# nfc_3911_sch.net
KiCad netlist of a schematic drawn in Altium Designer
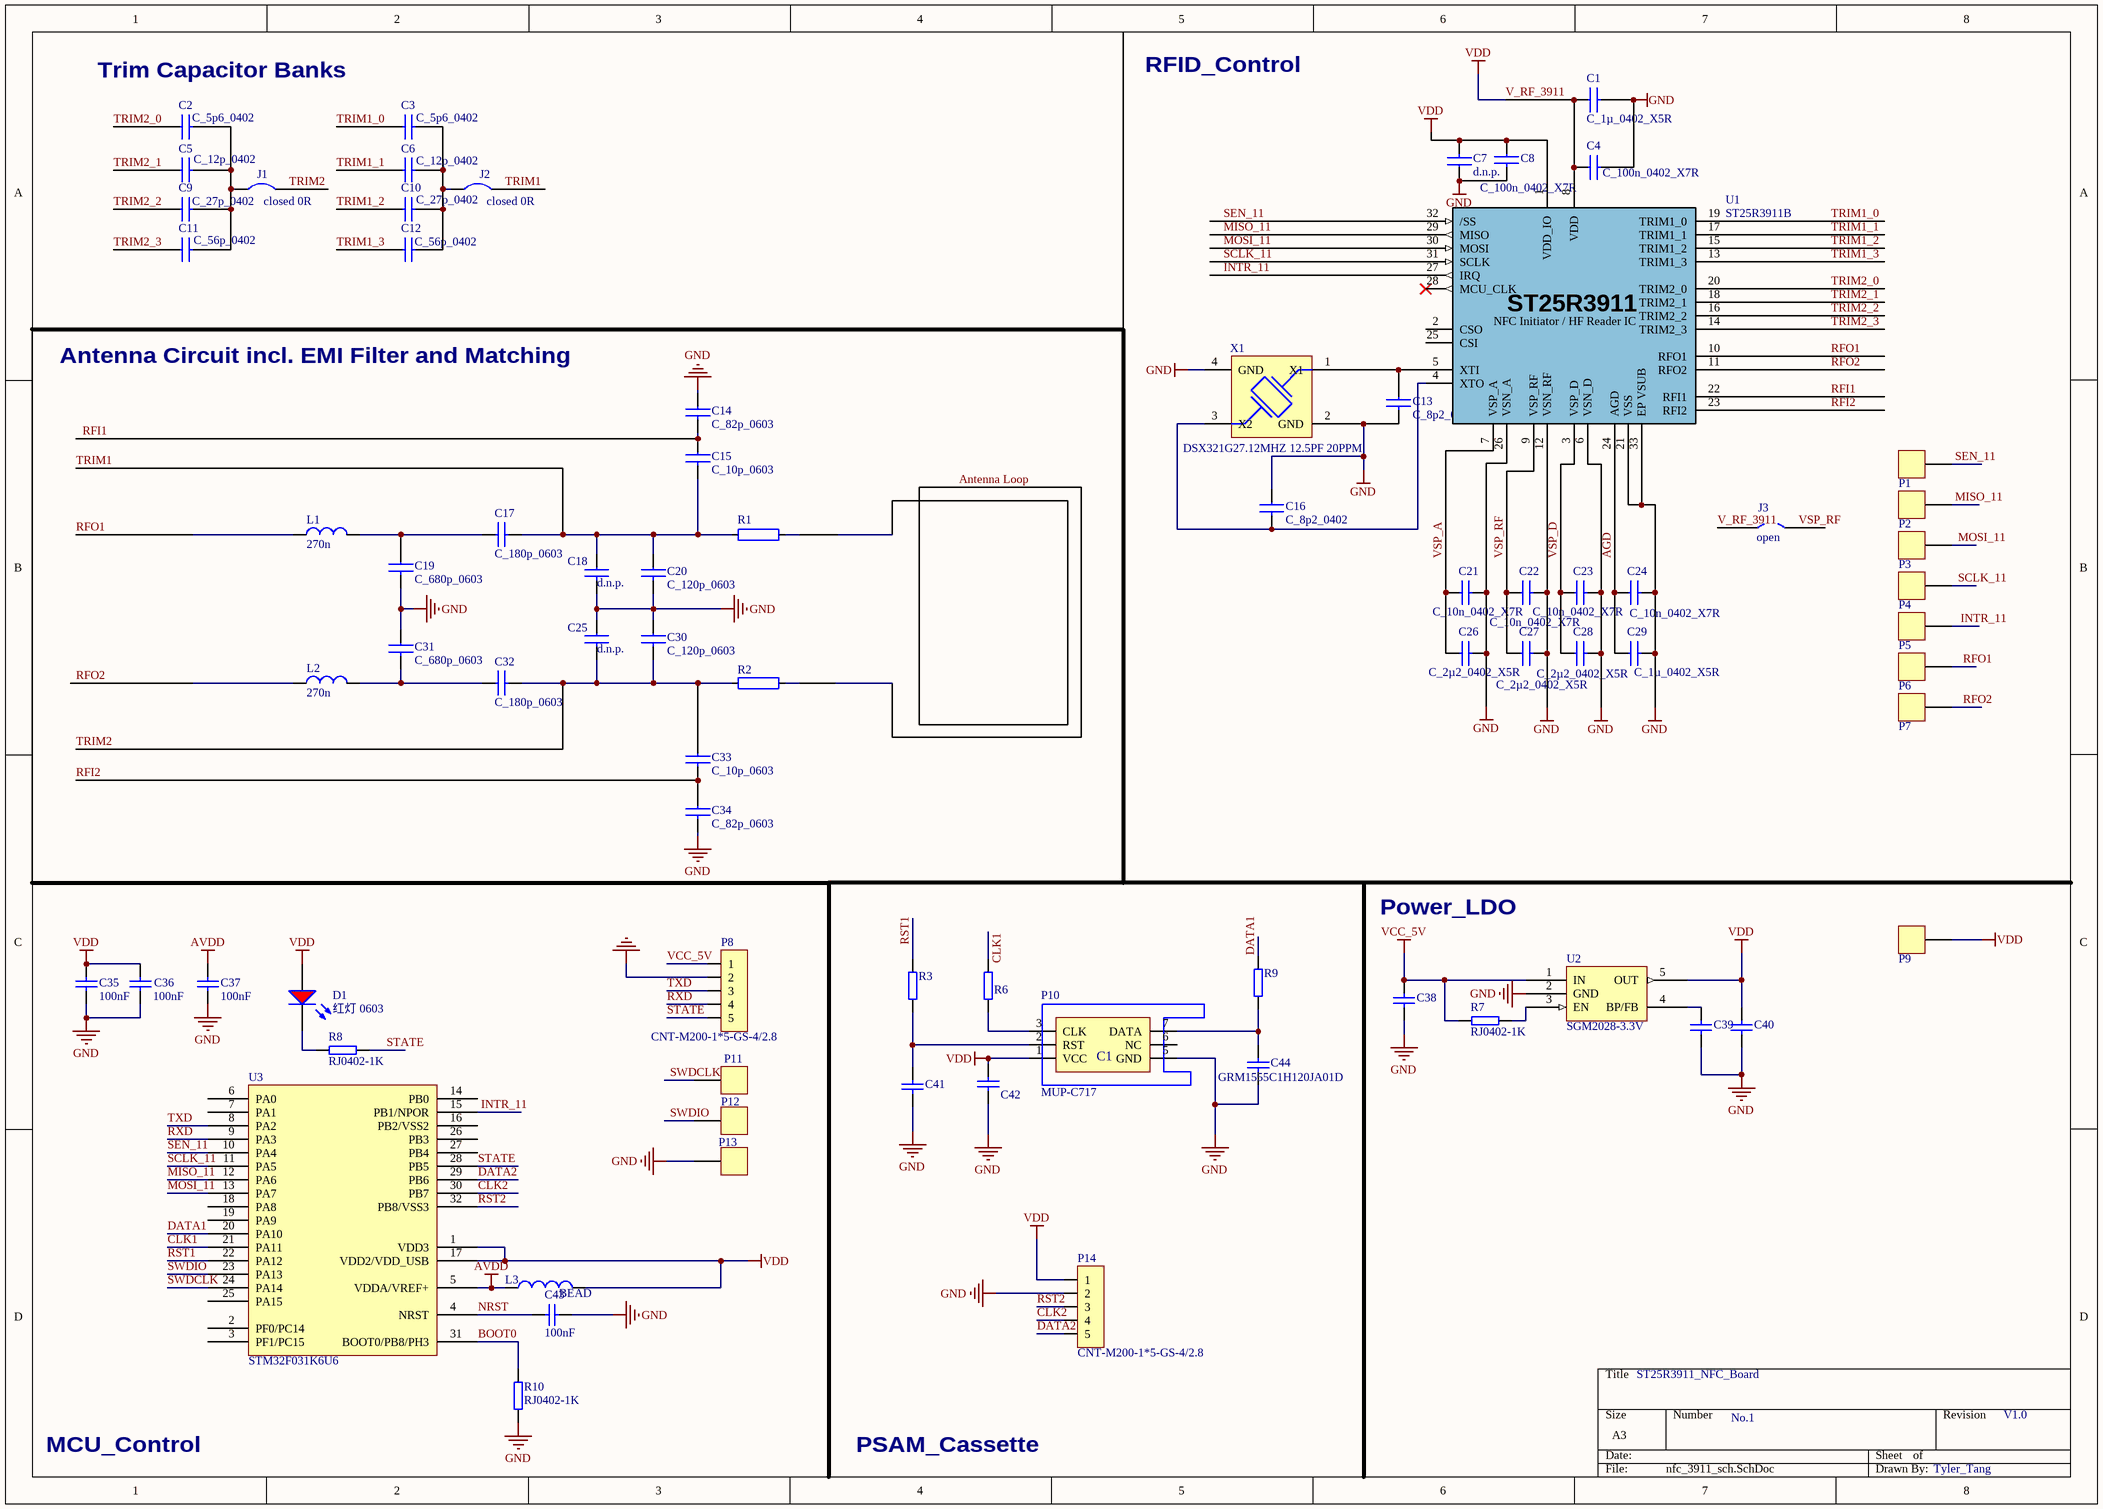
[diagram p0: nfc_3911_sch.SchDoc]

(export (version "E")
  (design (tool "Eeschema 10.0.6"))
  (components
    (comp (ref "C1")
      (value "C_1µ_0402_X5R")
      (footprint "0402_C")
      (description "1u_X5R")
      (fields
        (field (name "MANUFACTURER") "MURATA")
        (field (name "MANUFACTURER PART NUMBER") "GRM155R61C105KA12D")
      )
      (libsource (lib "Schlib1") (part "C_1µ_0402_X5R"))
    )
    (comp (ref "C2")
      (value "C_5p6_0402")
      (footprint "0402_C")
      (description "5p6_COG")
      (fields
        (field (name "MANUFACTURER") "MURATA")
        (field (name "MANUFACTURER PART NUMBER") "GRM1555C1H5R6DA01D")
      )
      (libsource (lib "Schlib1") (part "C_5p6_0402"))
    )
    (comp (ref "C3")
      (value "C_5p6_0402")
      (footprint "0402_C")
      (description "5p6_COG")
      (fields
        (field (name "MANUFACTURER") "MURATA")
        (field (name "MANUFACTURER PART NUMBER") "GRM1555C1H5R6DA01D")
      )
      (libsource (lib "Schlib1") (part "C_5p6_0402"))
    )
    (comp (ref "C4")
      (value "C_100n_0402_X7R")
      (footprint "0402_C")
      (description "100n_X7R")
      (fields
        (field (name "MANUFACTURER") "MULTICOMP")
        (field (name "MANUFACTURER PART NUMBER") "MC0402X104K100CT")
      )
      (libsource (lib "Schlib1") (part "C_100n_0402_X7R"))
    )
    (comp (ref "C5")
      (value "C_12p_0402")
      (footprint "0402_C")
      (description "12p_COG")
      (fields
        (field (name "MANUFACTURER") "MURATA")
        (field (name "MANUFACTURER PART NUMBER") "GRM1555C1H120GA01D")
      )
      (libsource (lib "Schlib1") (part "C_12p_0402"))
    )
    (comp (ref "C6")
      (value "C_12p_0402")
      (footprint "0402_C")
      (description "12p_COG")
      (fields
        (field (name "MANUFACTURER") "MURATA")
        (field (name "MANUFACTURER PART NUMBER") "GRM1555C1H120GA01D")
      )
      (libsource (lib "Schlib1") (part "C_12p_0402"))
    )
    (comp (ref "C7") (value "d.n.p.") (footprint "0402_C") (libsource (lib "PASSIVE_082011") (part "C_0402")))
    (comp (ref "C8")
      (value "C_100n_0402_X7R")
      (footprint "0402_C")
      (description "100n_X7R")
      (fields
        (field (name "MANUFACTURER") "MULTICOMP")
        (field (name "MANUFACTURER PART NUMBER") "MC0402X104K100CT")
      )
      (libsource (lib "Schlib1") (part "C_100n_0402_X7R"))
    )
    (comp (ref "C9")
      (value "C_27p_0402")
      (footprint "0402_C")
      (description "27p_COG")
      (fields
        (field (name "MANUFACTURER") "MURATA")
        (field (name "MANUFACTURER PART NUMBER") "GRM1555C1H270GA01D")
      )
      (libsource (lib "Schlib1") (part "C_27p_0402"))
    )
    (comp (ref "C10")
      (value "C_27p_0402")
      (footprint "0402_C")
      (description "27p_COG")
      (fields
        (field (name "MANUFACTURER") "MURATA")
        (field (name "MANUFACTURER PART NUMBER") "GRM1555C1H270GA01D")
      )
      (libsource (lib "Schlib1") (part "C_27p_0402"))
    )
    (comp (ref "C11")
      (value "C_56p_0402")
      (footprint "0402_C")
      (description "56p_COG")
      (fields
        (field (name "MANUFACTURER") "MURATA")
        (field (name "MANUFACTURER PART NUMBER") "GRM1555C1H560GA01D")
      )
      (libsource (lib "Schlib1") (part "C_56p_0402"))
    )
    (comp (ref "C12")
      (value "C_56p_0402")
      (footprint "0402_C")
      (description "56p_COG")
      (fields
        (field (name "MANUFACTURER") "MURATA")
        (field (name "MANUFACTURER PART NUMBER") "GRM1555C1H560GA01D")
      )
      (libsource (lib "Schlib1") (part "C_56p_0402"))
    )
    (comp (ref "C13")
      (value "C_8p2_0402")
      (footprint "0402_C")
      (description "8p2_COG")
      (fields
        (field (name "MANUFACTURER") "MURATA")
        (field (name "MANUFACTURER PART NUMBER") "GRM1555C1H8R2CA01D")
      )
      (libsource (lib "Schlib1") (part "C_8p2_0402"))
    )
    (comp (ref "C14")
      (value "C_82p_0603")
      (footprint "0603_C")
      (description "82p_COG")
      (fields
        (field (name "MANUFACTURER") "MURATA")
        (field (name "MANUFACTURER PART NUMBER") "GRM1885C1H820FA01D")
      )
      (libsource (lib "Schlib1") (part "C_82p_0603"))
    )
    (comp (ref "C15")
      (value "C_10p_0603")
      (footprint "0603_C")
      (description "10p_COG")
      (fields
        (field (name "MANUFACTURER") "MULTICOMP")
        (field (name "MANUFACTURER PART NUMBER") "MC0603N100F500CT")
      )
      (libsource (lib "Schlib1") (part "C_10p_0603"))
    )
    (comp (ref "C16")
      (value "C_8p2_0402")
      (footprint "0402_C")
      (description "8p2_COG")
      (fields
        (field (name "MANUFACTURER") "MURATA")
        (field (name "MANUFACTURER PART NUMBER") "GRM1555C1H8R2CA01D")
      )
      (libsource (lib "Schlib1") (part "C_8p2_0402"))
    )
    (comp (ref "C17")
      (value "C_180p_0603")
      (footprint "0603_C")
      (description "180p_COG")
      (fields
        (field (name "MANUFACTURER") "MURATA")
        (field (name "MANUFACTURER PART NUMBER") "GRM1885C1H181GA01D")
      )
      (libsource (lib "Schlib1") (part "C_180p_0603"))
    )
    (comp (ref "C18")
      (value "d.n.p.")
      (footprint "0603_C")
      (libsource (lib "PASSIVE_082011") (part "C_0603"))
    )
    (comp (ref "C19")
      (value "C_680p_0603")
      (footprint "0603_C")
      (description "680p_COG")
      (fields
        (field (name "MANUFACTURER") "MURATA")
        (field (name "MANUFACTURER PART NUMBER") "GRM1885C1H681GA01D")
      )
      (libsource (lib "Schlib1") (part "C_680p_0603"))
    )
    (comp (ref "C20")
      (value "C_120p_0603")
      (footprint "0603_C")
      (description "120p_COG")
      (fields
        (field (name "MANUFACTURER") "MURATA")
        (field (name "MANUFACTURER PART NUMBER") "GRM1885C1H121GA01D")
      )
      (libsource (lib "Schlib1") (part "C_120p_0603"))
    )
    (comp (ref "C21")
      (value "C_10n_0402_X7R")
      (footprint "0402_C")
      (description "10n_x7R")
      (fields (field (name "MANUFACTURER") "AVX") (field (name "MANUFACTURER PART NUMBER") "04023C103KAT2A"))
      (libsource (lib "Schlib1") (part "C_10n_0402_X7R"))
    )
    (comp (ref "C22")
      (value "C_10n_0402_X7R")
      (footprint "0402_C")
      (description "10n_x7R")
      (fields (field (name "MANUFACTURER") "AVX") (field (name "MANUFACTURER PART NUMBER") "04023C103KAT2A"))
      (libsource (lib "Schlib1") (part "C_10n_0402_X7R"))
    )
    (comp (ref "C23")
      (value "C_10n_0402_X7R")
      (footprint "0402_C")
      (description "10n_x7R")
      (fields (field (name "MANUFACTURER") "AVX") (field (name "MANUFACTURER PART NUMBER") "04023C103KAT2A"))
      (libsource (lib "Schlib1") (part "C_10n_0402_X7R"))
    )
    (comp (ref "C24")
      (value "C_10n_0402_X7R")
      (footprint "0402_C")
      (description "10n_x7R")
      (fields (field (name "MANUFACTURER") "AVX") (field (name "MANUFACTURER PART NUMBER") "04023C103KAT2A"))
      (libsource (lib "Schlib1") (part "C_10n_0402_X7R"))
    )
    (comp (ref "C25")
      (value "d.n.p.")
      (footprint "0603_C")
      (libsource (lib "PASSIVE_082011") (part "C_0603"))
    )
    (comp (ref "C26")
      (value "C_2µ2_0402_X5R")
      (footprint "0402_C")
      (description "2u2_X5R")
      (fields
        (field (name "MANUFACTURER") "MURATA")
        (field (name "MANUFACTURER PART NUMBER") "GRM155R60J225ME15D")
      )
      (libsource (lib "Schlib1") (part "C_2µ2_0402_X5R"))
    )
    (comp (ref "C27")
      (value "C_2µ2_0402_X5R")
      (footprint "0402_C")
      (description "2u2_X5R")
      (fields
        (field (name "MANUFACTURER") "MURATA")
        (field (name "MANUFACTURER PART NUMBER") "GRM155R60J225ME15D")
      )
      (libsource (lib "Schlib1") (part "C_2µ2_0402_X5R"))
    )
    (comp (ref "C28")
      (value "C_2µ2_0402_X5R")
      (footprint "0402_C")
      (description "2u2_X5R")
      (fields
        (field (name "MANUFACTURER") "MURATA")
        (field (name "MANUFACTURER PART NUMBER") "GRM155R60J225ME15D")
      )
      (libsource (lib "Schlib1") (part "C_2µ2_0402_X5R"))
    )
    (comp (ref "C29")
      (value "C_1µ_0402_X5R")
      (footprint "0402_C")
      (description "1u_X5R")
      (fields
        (field (name "MANUFACTURER") "MURATA")
        (field (name "MANUFACTURER PART NUMBER") "GRM155R61C105KA12D")
      )
      (libsource (lib "Schlib1") (part "C_1µ_0402_X5R"))
    )
    (comp (ref "C30")
      (value "C_120p_0603")
      (footprint "0603_C")
      (description "120p_COG")
      (fields
        (field (name "MANUFACTURER") "MURATA")
        (field (name "MANUFACTURER PART NUMBER") "GRM1885C1H121GA01D")
      )
      (libsource (lib "Schlib1") (part "C_120p_0603"))
    )
    (comp (ref "C31")
      (value "C_680p_0603")
      (footprint "0603_C")
      (description "680p_COG")
      (fields
        (field (name "MANUFACTURER") "MURATA")
        (field (name "MANUFACTURER PART NUMBER") "GRM1885C1H681GA01D")
      )
      (libsource (lib "Schlib1") (part "C_680p_0603"))
    )
    (comp (ref "C32")
      (value "C_180p_0603")
      (footprint "0603_C")
      (description "180p_COG")
      (fields
        (field (name "MANUFACTURER") "MURATA")
        (field (name "MANUFACTURER PART NUMBER") "GRM1885C1H181GA01D")
      )
      (libsource (lib "Schlib1") (part "C_180p_0603"))
    )
    (comp (ref "C33")
      (value "C_10p_0603")
      (footprint "0603_C")
      (description "10p_COG")
      (fields
        (field (name "MANUFACTURER") "MULTICOMP")
        (field (name "MANUFACTURER PART NUMBER") "MC0603N100F500CT")
      )
      (libsource (lib "Schlib1") (part "C_10p_0603"))
    )
    (comp (ref "C34")
      (value "C_82p_0603")
      (footprint "0603_C")
      (description "82p_COG")
      (fields
        (field (name "MANUFACTURER") "MURATA")
        (field (name "MANUFACTURER PART NUMBER") "GRM1885C1H820FA01D")
      )
      (libsource (lib "Schlib1") (part "C_82p_0603"))
    )
    (comp (ref "C35")
      (value "100nF")
      (footprint "0402_C")
      (description "Capacitor")
      (fields (field (name "PUBLISHER") "Altium Limited"))
      (libsource (lib "Miscellaneous Devices") (part "Cap"))
    )
    (comp (ref "C36")
      (value "100nF")
      (footprint "0402_C")
      (description "Capacitor")
      (fields (field (name "PUBLISHER") "Altium Limited"))
      (libsource (lib "Miscellaneous Devices") (part "Cap"))
    )
    (comp (ref "C37")
      (value "100nF")
      (footprint "0402_C")
      (description "Capacitor")
      (fields (field (name "PUBLISHER") "Altium Limited"))
      (libsource (lib "Miscellaneous Devices") (part "Cap"))
    )
    (comp (ref "C38")
      (value "CAP-NP")
      (footprint "0402_C")
      (description "1uF/6.3V/10%/X5R")
      (libsource (lib "LSD Altium") (part "CAP-NP"))
    )
    (comp (ref "C39")
      (value "CAP-NP")
      (footprint "0402_C")
      (description "1uF/6.3V/10%/X5R")
      (libsource (lib "LSD Altium") (part "CAP-NP"))
    )
    (comp (ref "C40")
      (value "CAP-NP")
      (footprint "0402_C")
      (description "10nF/25V/10%/X7R")
      (libsource (lib "LSD Altium") (part "CAP-NP"))
    )
    (comp (ref "C41")
      (value "CAP-NP")
      (footprint "0402_C")
      (description "0.1uF/16V/10%/X5R")
      (libsource (lib "LSD Altium") (part "CAP-NP"))
    )
    (comp (ref "C42")
      (value "CAP-NP")
      (footprint "0402_C")
      (description "0.1uF/16V/10%/X5R")
      (libsource (lib "LSD Altium") (part "CAP-NP"))
    )
    (comp (ref "C43")
      (value "100nF")
      (footprint "0402_C")
      (description "Capacitor")
      (fields (field (name "PUBLISHER") "Altium Limited"))
      (libsource (lib "Miscellaneous Devices") (part "CAP"))
    )
    (comp (ref "C44")
      (value "CAP-NP")
      (footprint "0402C_0.4D")
      (description "12pF/50V/5%/C0G")
      (fields (field (name "产品型号") "GRM1555C1H120JA01D"))
      (libsource (lib "LSD Altium") (part "CAP-NP"))
    )
    (comp (ref "D1")
      (value "红灯 0603")
      (footprint "0603_LED_S1")
      (description "发光二极管")
      (libsource (lib "LED") (part "0603 红灯"))
    )
    (comp (ref "J1")
      (value "closed 0R")
      (footprint "0402_R")
      (description "0R")
      (fields
        (field (name "MANUFACTURER") "Multicomp")
        (field (name "MANUFACTURER PART NUMBER") "MC00625W040210R")
      )
      (libsource (lib "Schlib1") (part "solder_jumper_closed"))
    )
    (comp (ref "J2")
      (value "closed 0R")
      (footprint "0402_R")
      (description "0R")
      (fields
        (field (name "MANUFACTURER") "Multicomp")
        (field (name "MANUFACTURER PART NUMBER") "MC00625W040210R")
      )
      (libsource (lib "Schlib1") (part "solder_jumper_closed"))
    )
    (comp (ref "J3")
      (value "open")
      (footprint "0402_R")
      (libsource (lib "Schlib1") (part "solder_jumper_open"))
    )
    (comp (ref "L1")
      (value "270n")
      (footprint "0603_L")
      (description "L0603_270nH")
      (fields
        (field (name "MANUFACTURER") "MURATA")
        (field (name "MANUFACTURER PART NUMBER") "LQW18ANR27G80D")
      )
      (libsource (lib "Schlib1") (part "L0603_270nH"))
    )
    (comp (ref "L2")
      (value "270n")
      (footprint "0603_L")
      (description "L0603_270nH")
      (fields
        (field (name "MANUFACTURER") "MURATA")
        (field (name "MANUFACTURER PART NUMBER") "LQW18ANR27G80D")
      )
      (libsource (lib "Schlib1") (part "L0603_270nH"))
    )
    (comp (ref "L3")
      (value "BEAD")
      (footprint "0603")
      (description "Inductor")
      (fields (field (name "PUBLISHER") "Altium Limited"))
      (libsource (lib "Miscellaneous Devices") (part "Inductor"))
    )
    (comp (ref "P1") (value "Hole") (footprint "TP1") (libsource (lib "4_1 EcoSys") (part "Hole")))
    (comp (ref "P2") (value "Hole") (footprint "TP1") (libsource (lib "4_1 EcoSys") (part "Hole")))
    (comp (ref "P3") (value "Hole") (footprint "TP1") (libsource (lib "4_1 EcoSys") (part "Hole")))
    (comp (ref "P4") (value "Hole") (footprint "TP1") (libsource (lib "4_1 EcoSys") (part "Hole")))
    (comp (ref "P5") (value "Hole") (footprint "TP1") (libsource (lib "4_1 EcoSys") (part "Hole")))
    (comp (ref "P6") (value "Hole") (footprint "TP1") (libsource (lib "4_1 EcoSys") (part "Hole")))
    (comp (ref "P7") (value "Hole") (footprint "TP1") (libsource (lib "4_1 EcoSys") (part "Hole")))
    (comp (ref "P8")
      (value "SPI 5-M")
      (footprint "SIP 2.0_5_S")
      (description "2.00mm/1*5P/单排/直/PA=4/PC=2.8")
      (fields (field (name "产品型号") "CNT-M200-1*5-GS-4/2.8"))
      (libsource (lib "LSD Altium") (part "SPI 5-M"))
    )
    (comp (ref "P9") (value "Hole") (footprint "TP1") (libsource (lib "4_1 EcoSys") (part "Hole")))
    (comp (ref "P10")
      (value "SIM-4")
      (footprint "SIM-MUP-C717")
      (description "SIM卡座")
      (fields (field (name "产品型号") "MUP-C717"))
      (libsource (lib "LSD Altium") (part "SIM-4"))
    )
    (comp (ref "P11") (value "Hole") (footprint "TP1") (libsource (lib "") (part "Hole_1")))
    (comp (ref "P12") (value "Hole") (footprint "TP1") (libsource (lib "") (part "Hole_1")))
    (comp (ref "P13") (value "Hole") (footprint "TP1") (libsource (lib "") (part "Hole_1")))
    (comp (ref "P14")
      (value "SPI 5-M")
      (footprint "SIP 2.0_5_S")
      (description "2.00mm/1*5P/单排/直/PA=4/PC=2.8")
      (fields (field (name "产品型号") "CNT-M200-1*5-GS-4/2.8"))
      (libsource (lib "LSD Altium") (part "SPI 5-M"))
    )
    (comp (ref "R1")
      (value "3R9")
      (footprint "0603_R")
      (description "3R9, 0603")
      (fields
        (field (name "MANUFACTURER") "Panasonic")
        (field (name "MANUFACTURER PART NUMBER") "ERJ-3GEYJ3R9V")
      )
      (libsource (lib "Schlib1") (part "R0603_3R9"))
    )
    (comp (ref "R2")
      (value "3R9")
      (footprint "0603_R")
      (description "3R9, 0603")
      (fields
        (field (name "MANUFACTURER") "Panasonic")
        (field (name "MANUFACTURER PART NUMBER") "ERJ-3GEYJ3R9V")
      )
      (libsource (lib "Schlib1") (part "R0603_3R9"))
    )
    (comp (ref "R3")
      (value "RES")
      (footprint "0402R_0.4D")
      (description "33R/5%/100PPM")
      (libsource (lib "LSD Altium") (part "RES"))
    )
    (comp (ref "R6")
      (value "RES")
      (footprint "0402R_0.4D")
      (description "33R/5%/100PPM")
      (libsource (lib "LSD Altium") (part "RES"))
    )
    (comp (ref "R7")
      (value "RES")
      (footprint "0402R_0.4D")
      (description "1K/5%/100PPM")
      (fields (field (name "产品型号") "RJ0402-1K"))
      (libsource (lib "LSD Altium") (part "RES"))
    )
    (comp (ref "R8")
      (value "RES")
      (footprint "0402R_0.4D")
      (description "1K/5%/100PPM")
      (fields (field (name "产品型号") "RJ0402-1K"))
      (libsource (lib "LSD Altium") (part "RES"))
    )
    (comp (ref "R9")
      (value "RES")
      (footprint "0402R_0.4D")
      (description "33R/5%/100PPM")
      (libsource (lib "LSD Altium") (part "RES"))
    )
    (comp (ref "R10")
      (value "RES")
      (footprint "0402R_0.4D")
      (description "1K/5%/100PPM")
      (fields (field (name "产品型号") "RJ0402-1K"))
      (libsource (lib "LSD Altium") (part "RES"))
    )
    (comp (ref "U1")
      (value "ST25R3911B")
      (footprint "ST25R3911B")
      (description "NFC Initiator / HF Reader IC")
      (fields
        (field (name "MANUFACTURER") "STMicroelectronics")
        (field (name "MANUFACTURER PART NUMBER") "ST25R3911B-AQFMCT-ND")
      )
      (libsource (lib "Schlib1") (part "ST25R3911"))
    )
    (comp (ref "U2")
      (value "SGM2028-3.3V")
      (footprint "SGM2028-3.3")
      (libsource (lib "nfc_3911_schLib") (part "SGM2028"))
    )
    (comp (ref "U3")
      (value "STM32F031K6U6")
      (footprint "STM32F031K6U6")
      (libsource (lib "MB1180") (part "MCU_LQFP32"))
    )
    (comp (ref "X1")
      (value "CRYSTAL-4P")
      (footprint "2520")
      (description "10pF/40MHz/10PPM/60Ωmax/-40°~85°")
      (fields (field (name "产品型号") "DSX321G27.12MHZ 12.5PF 20PPM"))
      (libsource (lib "LSD Altium") (part "CRYSTAL-4P"))
    )
  )
  (nets
    (net (code "1") (name "/AGD") (class "Default")
      (node (ref "C24") (pin "1") (pinfunction "1_1") (pintype "passive"))
      (node (ref "C29") (pin "1") (pinfunction "1_1") (pintype "passive"))
      (node (ref "U1") (pin "24") (pinfunction "AGD_24") (pintype "passive"))
    )
    (net (code "2") (name "/Antenna Loop") (class "Default")
      (node (ref "R1") (pin "1") (pinfunction "1_1") (pintype "passive"))
      (node (ref "R2") (pin "1") (pinfunction "1_1") (pintype "passive"))
    )
    (net (code "3") (name "/BOOT0") (class "Default")
      (node (ref "R10") (pin "1") (pinfunction "1_1") (pintype "passive"))
      (node (ref "U3") (pin "31") (pinfunction "BOOT0/PB8/PH3_31") (pintype "passive"))
    )
    (net (code "4") (name "/CLK1") (class "Default")
      (node (ref "R6") (pin "1") (pinfunction "1_1") (pintype "passive"))
      (node (ref "U3") (pin "21") (pinfunction "PA11_21") (pintype "passive"))
    )
    (net (code "5") (name "/CLK2") (class "Default")
      (node (ref "P14") (pin "4") (pinfunction "4_4") (pintype "passive"))
      (node (ref "U3") (pin "30") (pinfunction "PB7_30") (pintype "passive"))
    )
    (net (code "6") (name "/DATA1") (class "Default")
      (node (ref "R9") (pin "2") (pinfunction "2_2") (pintype "passive"))
      (node (ref "U3") (pin "20") (pinfunction "PA10_20") (pintype "passive"))
    )
    (net (code "7") (name "/DATA2") (class "Default")
      (node (ref "P14") (pin "5") (pinfunction "5_5") (pintype "passive"))
      (node (ref "U3") (pin "29") (pinfunction "PB6_29") (pintype "passive"))
    )
    (net (code "8") (name "/INTR_11") (class "Default")
      (node (ref "P5") (pin "1") (pinfunction "1_1") (pintype "passive"))
      (node (ref "U1") (pin "27") (pinfunction "IRQ_27") (pintype "output"))
      (node (ref "U3") (pin "15") (pinfunction "PB1/NPOR_15") (pintype "passive"))
    )
    (net (code "9") (name "/MISO_11") (class "Default")
      (node (ref "P2") (pin "1") (pinfunction "1_1") (pintype "passive"))
      (node (ref "U1") (pin "29") (pinfunction "MISO_29") (pintype "output"))
      (node (ref "U3") (pin "12") (pinfunction "PA6_12") (pintype "passive"))
    )
    (net (code "10") (name "/MOSI_11") (class "Default")
      (node (ref "P3") (pin "1") (pinfunction "1_1") (pintype "passive"))
      (node (ref "U1") (pin "30") (pinfunction "MOSI_30") (pintype "input"))
      (node (ref "U3") (pin "13") (pinfunction "PA7_13") (pintype "passive"))
    )
    (net (code "11") (name "/NRST") (class "Default")
      (node (ref "C43") (pin "2") (pinfunction "2_2") (pintype "passive"))
      (node (ref "U3") (pin "4") (pinfunction "NRST_4") (pintype "passive"))
    )
    (net (code "12") (name "/RFI1") (class "Default")
      (node (ref "C14") (pin "2") (pinfunction "2_2") (pintype "passive"))
      (node (ref "C15") (pin "1") (pinfunction "1_1") (pintype "passive"))
      (node (ref "U1") (pin "22") (pinfunction "RFI1_22") (pintype "passive"))
    )
    (net (code "13") (name "/RFI2") (class "Default")
      (node (ref "C33") (pin "2") (pinfunction "2_2") (pintype "passive"))
      (node (ref "C34") (pin "1") (pinfunction "1_1") (pintype "passive"))
      (node (ref "U1") (pin "23") (pinfunction "RFI2_23") (pintype "passive"))
    )
    (net (code "14") (name "/RFO1") (class "Default")
      (node (ref "L1") (pin "2") (pinfunction "2_2") (pintype "passive"))
      (node (ref "P6") (pin "1") (pinfunction "1_1") (pintype "passive"))
      (node (ref "U1") (pin "10") (pinfunction "RFO1_10") (pintype "passive"))
    )
    (net (code "15") (name "/RFO2") (class "Default")
      (node (ref "L2") (pin "2") (pinfunction "2_2") (pintype "passive"))
      (node (ref "P7") (pin "1") (pinfunction "1_1") (pintype "passive"))
      (node (ref "U1") (pin "11") (pinfunction "RFO2_11") (pintype "passive"))
    )
    (net (code "16") (name "/RST1") (class "Default")
      (node (ref "R3") (pin "2") (pinfunction "2_2") (pintype "passive"))
      (node (ref "U3") (pin "22") (pinfunction "PA12_22") (pintype "passive"))
    )
    (net (code "17") (name "/RST2") (class "Default")
      (node (ref "P14") (pin "3") (pinfunction "3_3") (pintype "passive"))
      (node (ref "U3") (pin "32") (pinfunction "PB8/VSS3_32") (pintype "passive"))
    )
    (net (code "18") (name "/RXD") (class "Default")
      (node (ref "P8") (pin "4") (pinfunction "4_4") (pintype "passive"))
      (node (ref "U3") (pin "9") (pinfunction "PA3_9") (pintype "passive"))
    )
    (net (code "19") (name "/SCLK_11") (class "Default")
      (node (ref "P4") (pin "1") (pinfunction "1_1") (pintype "passive"))
      (node (ref "U1") (pin "31") (pinfunction "SCLK_31") (pintype "input"))
      (node (ref "U3") (pin "11") (pinfunction "PA5_11") (pintype "passive"))
    )
    (net (code "20") (name "/SEN_11") (class "Default")
      (node (ref "P1") (pin "1") (pinfunction "1_1") (pintype "passive"))
      (node (ref "U1") (pin "32") (pinfunction "/SS_32") (pintype "input"))
      (node (ref "U3") (pin "10") (pinfunction "PA4_10") (pintype "passive"))
    )
    (net (code "21") (name "/STATE") (class "Default")
      (node (ref "P8") (pin "5") (pinfunction "5_5") (pintype "passive"))
      (node (ref "R8") (pin "2") (pinfunction "2_2") (pintype "passive"))
      (node (ref "U3") (pin "28") (pinfunction "PB5_28") (pintype "passive"))
    )
    (net (code "22") (name "/SWDCLK") (class "Default")
      (node (ref "P11") (pin "1") (pinfunction "1_1") (pintype "passive"))
      (node (ref "U3") (pin "24") (pinfunction "PA14_24") (pintype "passive"))
    )
    (net (code "23") (name "/SWDIO") (class "Default")
      (node (ref "P12") (pin "1") (pinfunction "1_1") (pintype "passive"))
      (node (ref "U3") (pin "23") (pinfunction "PA13_23") (pintype "passive"))
    )
    (net (code "24") (name "/TRIM1") (class "Default")
      (node (ref "C15") (pin "2") (pinfunction "2_2") (pintype "passive"))
      (node (ref "C17") (pin "2") (pinfunction "2_2") (pintype "passive"))
      (node (ref "C18") (pin "1") (pinfunction "1_1") (pintype "passive"))
      (node (ref "C20") (pin "1") (pinfunction "1_1") (pintype "passive"))
      (node (ref "J2") (pin "2") (pinfunction "2_2") (pintype "passive"))
      (node (ref "R1") (pin "2") (pinfunction "2_2") (pintype "passive"))
    )
    (net (code "25") (name "/TRIM1_0") (class "Default")
      (node (ref "C3") (pin "1") (pinfunction "1_1") (pintype "passive"))
      (node (ref "U1") (pin "19") (pinfunction "TRIM1_0_19") (pintype "passive"))
    )
    (net (code "26") (name "/TRIM1_1") (class "Default")
      (node (ref "C6") (pin "1") (pinfunction "1_1") (pintype "passive"))
      (node (ref "U1") (pin "17") (pinfunction "TRIM1_1_17") (pintype "passive"))
    )
    (net (code "27") (name "/TRIM1_2") (class "Default")
      (node (ref "C10") (pin "1") (pinfunction "1_1") (pintype "passive"))
      (node (ref "U1") (pin "15") (pinfunction "TRIM1_2_15") (pintype "passive"))
    )
    (net (code "28") (name "/TRIM1_3") (class "Default")
      (node (ref "C12") (pin "1") (pinfunction "1_1") (pintype "passive"))
      (node (ref "U1") (pin "13") (pinfunction "TRIM1_3_13") (pintype "passive"))
    )
    (net (code "29") (name "/TRIM2") (class "Default")
      (node (ref "C25") (pin "2") (pinfunction "2_2") (pintype "passive"))
      (node (ref "C30") (pin "2") (pinfunction "2_2") (pintype "passive"))
      (node (ref "C32") (pin "2") (pinfunction "2_2") (pintype "passive"))
      (node (ref "C33") (pin "1") (pinfunction "1_1") (pintype "passive"))
      (node (ref "J1") (pin "2") (pinfunction "2_2") (pintype "passive"))
      (node (ref "R2") (pin "2") (pinfunction "2_2") (pintype "passive"))
    )
    (net (code "30") (name "/TRIM2_0") (class "Default")
      (node (ref "C2") (pin "1") (pinfunction "1_1") (pintype "passive"))
      (node (ref "U1") (pin "20") (pinfunction "TRIM2_0_20") (pintype "passive"))
    )
    (net (code "31") (name "/TRIM2_1") (class "Default")
      (node (ref "C5") (pin "1") (pinfunction "1_1") (pintype "passive"))
      (node (ref "U1") (pin "18") (pinfunction "TRIM2_1_18") (pintype "passive"))
    )
    (net (code "32") (name "/TRIM2_2") (class "Default")
      (node (ref "C9") (pin "1") (pinfunction "1_1") (pintype "passive"))
      (node (ref "U1") (pin "16") (pinfunction "TRIM2_2_16") (pintype "passive"))
    )
    (net (code "33") (name "/TRIM2_3") (class "Default")
      (node (ref "C11") (pin "1") (pinfunction "1_1") (pintype "passive"))
      (node (ref "U1") (pin "14") (pinfunction "TRIM2_3_14") (pintype "passive"))
    )
    (net (code "34") (name "/TXD") (class "Default")
      (node (ref "P8") (pin "3") (pinfunction "3_3") (pintype "passive"))
      (node (ref "U3") (pin "8") (pinfunction "PA2_8") (pintype "passive"))
    )
    (net (code "35") (name "/VSP_A") (class "Default")
      (node (ref "C21") (pin "1") (pinfunction "1_1") (pintype "passive"))
      (node (ref "C26") (pin "1") (pinfunction "1_1") (pintype "passive"))
      (node (ref "U1") (pin "7") (pinfunction "VSP_A_7") (pintype "passive"))
    )
    (net (code "36") (name "/VSP_D") (class "Default")
      (node (ref "C23") (pin "1") (pinfunction "1_1") (pintype "passive"))
      (node (ref "C28") (pin "1") (pinfunction "1_1") (pintype "passive"))
      (node (ref "U1") (pin "3") (pinfunction "VSP_D_3") (pintype "passive"))
    )
    (net (code "37") (name "/VSP_RF") (class "Default")
      (node (ref "C22") (pin "1") (pinfunction "1_1") (pintype "passive"))
      (node (ref "C27") (pin "1") (pinfunction "1_1") (pintype "passive"))
      (node (ref "J3") (pin "2") (pinfunction "2_2") (pintype "passive"))
      (node (ref "U1") (pin "9") (pinfunction "VSP_RF_9") (pintype "passive"))
    )
    (net (code "38") (name "AVDD") (class "Default")
      (node (ref "C37") (pin "1") (pinfunction "1_1") (pintype "passive"))
      (node (ref "L3") (pin "1") (pinfunction "1_1") (pintype "passive"))
      (node (ref "U3") (pin "5") (pinfunction "VDDA/VREF+_5") (pintype "passive"))
    )
    (net (code "39") (name "GND") (class "Default")
      (node (ref "C1") (pin "2") (pinfunction "2_2") (pintype "passive"))
      (node (ref "C13") (pin "2") (pinfunction "2_2") (pintype "passive"))
      (node (ref "C14") (pin "1") (pinfunction "1_1") (pintype "passive"))
      (node (ref "C16") (pin "1") (pinfunction "1_1") (pintype "passive"))
      (node (ref "C18") (pin "2") (pinfunction "2_2") (pintype "passive"))
      (node (ref "C19") (pin "2") (pinfunction "2_2") (pintype "passive"))
      (node (ref "C20") (pin "2") (pinfunction "2_2") (pintype "passive"))
      (node (ref "C21") (pin "2") (pinfunction "2_2") (pintype "passive"))
      (node (ref "C22") (pin "2") (pinfunction "2_2") (pintype "passive"))
      (node (ref "C23") (pin "2") (pinfunction "2_2") (pintype "passive"))
      (node (ref "C24") (pin "2") (pinfunction "2_2") (pintype "passive"))
      (node (ref "C25") (pin "1") (pinfunction "1_1") (pintype "passive"))
      (node (ref "C26") (pin "2") (pinfunction "2_2") (pintype "passive"))
      (node (ref "C27") (pin "2") (pinfunction "2_2") (pintype "passive"))
      (node (ref "C28") (pin "2") (pinfunction "2_2") (pintype "passive"))
      (node (ref "C29") (pin "2") (pinfunction "2_2") (pintype "passive"))
      (node (ref "C30") (pin "1") (pinfunction "1_1") (pintype "passive"))
      (node (ref "C31") (pin "1") (pinfunction "1_1") (pintype "passive"))
      (node (ref "C34") (pin "2") (pinfunction "2_2") (pintype "passive"))
      (node (ref "C35") (pin "2") (pinfunction "2_2") (pintype "passive"))
      (node (ref "C36") (pin "2") (pinfunction "2_2") (pintype "passive"))
      (node (ref "C37") (pin "2") (pinfunction "2_2") (pintype "passive"))
      (node (ref "C38") (pin "1") (pintype "passive"))
      (node (ref "C39") (pin "1") (pintype "passive"))
      (node (ref "C4") (pin "2") (pinfunction "2_2") (pintype "passive"))
      (node (ref "C40") (pin "1") (pintype "passive"))
      (node (ref "C41") (pin "1") (pintype "passive"))
      (node (ref "C42") (pin "2") (pintype "passive"))
      (node (ref "C43") (pin "1") (pinfunction "1_1") (pintype "passive"))
      (node (ref "C44") (pin "1") (pintype "passive"))
      (node (ref "C7") (pin "1") (pinfunction "1_1") (pintype "passive"))
      (node (ref "C8") (pin "2") (pinfunction "2_2") (pintype "passive"))
      (node (ref "P10") (pin "5") (pinfunction "GND_5") (pintype "power_in"))
      (node (ref "P13") (pin "1") (pinfunction "1_1") (pintype "passive"))
      (node (ref "P14") (pin "2") (pinfunction "2_2") (pintype "passive"))
      (node (ref "P8") (pin "2") (pinfunction "2_2") (pintype "passive"))
      (node (ref "R10") (pin "2") (pinfunction "2_2") (pintype "passive"))
      (node (ref "U1") (pin "12") (pinfunction "VSN_RF_12") (pintype "power_in"))
      (node (ref "U1") (pin "21") (pinfunction "VSS_21") (pintype "power_in"))
      (node (ref "U1") (pin "26") (pinfunction "VSN_A_26") (pintype "power_in"))
      (node (ref "U1") (pin "33") (pinfunction "EP_VSUB_33") (pintype "passive"))
      (node (ref "U1") (pin "6") (pinfunction "VSN_D_6") (pintype "power_in"))
      (node (ref "U2") (pin "2") (pinfunction "GND_2") (pintype "power_in"))
      (node (ref "X1") (pin "2") (pinfunction "GND_2") (pintype "passive"))
      (node (ref "X1") (pin "4") (pinfunction "GND_4") (pintype "passive"))
    )
    (net (code "40") (name "Net-(C10-Pad2)") (class "Default")
      (node (ref "C10") (pin "2") (pinfunction "2_2") (pintype "passive"))
      (node (ref "C12") (pin "2") (pinfunction "2_2") (pintype "passive"))
      (node (ref "C3") (pin "2") (pinfunction "2_2") (pintype "passive"))
      (node (ref "C6") (pin "2") (pinfunction "2_2") (pintype "passive"))
      (node (ref "J2") (pin "1") (pinfunction "1_1") (pintype "passive"))
    )
    (net (code "41") (name "Net-(C11-Pad2)") (class "Default")
      (node (ref "C11") (pin "2") (pinfunction "2_2") (pintype "passive"))
      (node (ref "C2") (pin "2") (pinfunction "2_2") (pintype "passive"))
      (node (ref "C5") (pin "2") (pinfunction "2_2") (pintype "passive"))
      (node (ref "C9") (pin "2") (pinfunction "2_2") (pintype "passive"))
      (node (ref "J1") (pin "1") (pinfunction "1_1") (pintype "passive"))
    )
    (net (code "42") (name "Net-(C17-Pad1)") (class "Default")
      (node (ref "C17") (pin "1") (pinfunction "1_1") (pintype "passive"))
      (node (ref "C19") (pin "1") (pinfunction "1_1") (pintype "passive"))
      (node (ref "L1") (pin "1") (pinfunction "1_1") (pintype "passive"))
    )
    (net (code "43") (name "Net-(C31-Pad2)") (class "Default")
      (node (ref "C31") (pin "2") (pinfunction "2_2") (pintype "passive"))
      (node (ref "C32") (pin "1") (pinfunction "1_1") (pintype "passive"))
      (node (ref "L2") (pin "1") (pinfunction "1_1") (pintype "passive"))
    )
    (net (code "44") (name "Net-(D1-PadK)") (class "Default")
      (node (ref "D1") (pin "K") (pinfunction "K_K") (pintype "passive"))
      (node (ref "R8") (pin "1") (pinfunction "1_1") (pintype "passive"))
    )
    (net (code "45") (name "Net-(P10-CLK)") (class "Default")
      (node (ref "P10") (pin "3") (pinfunction "CLK_3") (pintype "passive"))
      (node (ref "R6") (pin "2") (pinfunction "2_2") (pintype "passive"))
    )
    (net (code "46") (name "Net-(P10-DATA)") (class "Default")
      (node (ref "C44") (pin "2") (pintype "passive"))
      (node (ref "P10") (pin "7") (pinfunction "DATA_7") (pintype "passive"))
      (node (ref "R9") (pin "1") (pinfunction "1_1") (pintype "passive"))
    )
    (net (code "47") (name "Net-(P10-RST)") (class "Default")
      (node (ref "C41") (pin "2") (pintype "passive"))
      (node (ref "P10") (pin "2") (pinfunction "RST_2") (pintype "passive"))
      (node (ref "R3") (pin "1") (pinfunction "1_1") (pintype "passive"))
    )
    (net (code "48") (name "Net-(U1-XTI)") (class "Default")
      (node (ref "C13") (pin "1") (pinfunction "1_1") (pintype "passive"))
      (node (ref "U1") (pin "5") (pinfunction "XTI_5") (pintype "passive"))
      (node (ref "X1") (pin "1") (pinfunction "X1_1") (pintype "passive"))
    )
    (net (code "49") (name "Net-(U1-XTO)") (class "Default")
      (node (ref "C16") (pin "2") (pinfunction "2_2") (pintype "passive"))
      (node (ref "U1") (pin "4") (pinfunction "XTO_4") (pintype "passive"))
      (node (ref "X1") (pin "3") (pinfunction "X2_3") (pintype "passive"))
    )
    (net (code "50") (name "Net-(U2-BP{slash}FB)") (class "Default")
      (node (ref "C39") (pin "2") (pintype "passive"))
      (node (ref "U2") (pin "4") (pinfunction "BP/FB_4") (pintype "passive"))
    )
    (net (code "51") (name "Net-(U2-EN)") (class "Default")
      (node (ref "R7") (pin "2") (pinfunction "2_2") (pintype "passive"))
      (node (ref "U2") (pin "3") (pinfunction "EN_3") (pintype "input"))
    )
    (net (code "52") (name "VCC_5V") (class "Default")
      (node (ref "C38") (pin "2") (pintype "passive"))
      (node (ref "P8") (pin "1") (pinfunction "1_1") (pintype "passive"))
      (node (ref "R7") (pin "1") (pinfunction "1_1") (pintype "passive"))
      (node (ref "U2") (pin "1") (pinfunction "IN_1") (pintype "power_in"))
    )
    (net (code "53") (name "VDD") (class "Default")
      (node (ref "C1") (pin "1") (pinfunction "1_1") (pintype "passive"))
      (node (ref "C35") (pin "1") (pinfunction "1_1") (pintype "passive"))
      (node (ref "C36") (pin "1") (pinfunction "1_1") (pintype "passive"))
      (node (ref "C4") (pin "1") (pinfunction "1_1") (pintype "passive"))
      (node (ref "C40") (pin "2") (pintype "passive"))
      (node (ref "C42") (pin "1") (pintype "passive"))
      (node (ref "C7") (pin "2") (pinfunction "2_2") (pintype "passive"))
      (node (ref "C8") (pin "1") (pinfunction "1_1") (pintype "passive"))
      (node (ref "D1") (pin "A") (pinfunction "A_A") (pintype "passive"))
      (node (ref "J3") (pin "1") (pinfunction "1_1") (pintype "passive"))
      (node (ref "L3") (pin "2") (pinfunction "2_2") (pintype "passive"))
      (node (ref "P10") (pin "1") (pinfunction "VCC_1") (pintype "power_in"))
      (node (ref "P14") (pin "1") (pinfunction "1_1") (pintype "passive"))
      (node (ref "P9") (pin "1") (pinfunction "1_1") (pintype "passive"))
      (node (ref "U1") (pin "1") (pinfunction "VDD_IO_1") (pintype "power_in"))
      (node (ref "U1") (pin "8") (pinfunction "VDD_8") (pintype "power_in"))
      (node (ref "U2") (pin "5") (pinfunction "OUT_5") (pintype "output"))
      (node (ref "U3") (pin "1") (pinfunction "VDD3_1") (pintype "passive"))
      (node (ref "U3") (pin "17") (pinfunction "VDD2/VDD_USB_17") (pintype "passive"))
    )
    (net (code "54") (name "unconnected-(P10-NC-Pad6)") (class "Default")
      (node (ref "P10") (pin "6") (pinfunction "NC_6") (pintype "power_in"))
    )
    (net (code "55") (name "unconnected-(U1-CSI-Pad25)") (class "Default")
      (node (ref "U1") (pin "25") (pinfunction "CSI_25") (pintype "passive"))
    )
    (net (code "56") (name "unconnected-(U1-CSO-Pad2)") (class "Default")
      (node (ref "U1") (pin "2") (pinfunction "CSO_2") (pintype "passive"))
    )
    (net (code "57") (name "unconnected-(U1-MCU_CLK-Pad28)") (class "Default")
      (node (ref "U1") (pin "28") (pinfunction "MCU_CLK_28") (pintype "output+no_connect"))
    )
    (net (code "58") (name "unconnected-(U3-PA0-Pad6)") (class "Default")
      (node (ref "U3") (pin "6") (pinfunction "PA0_6") (pintype "passive"))
    )
    (net (code "59") (name "unconnected-(U3-PA1-Pad7)") (class "Default")
      (node (ref "U3") (pin "7") (pinfunction "PA1_7") (pintype "passive"))
    )
    (net (code "60") (name "unconnected-(U3-PA8-Pad18)") (class "Default")
      (node (ref "U3") (pin "18") (pinfunction "PA8_18") (pintype "passive"))
    )
    (net (code "61") (name "unconnected-(U3-PA9-Pad19)") (class "Default")
      (node (ref "U3") (pin "19") (pinfunction "PA9_19") (pintype "passive"))
    )
    (net (code "62") (name "unconnected-(U3-PA15-Pad25)") (class "Default")
      (node (ref "U3") (pin "25") (pinfunction "PA15_25") (pintype "passive"))
    )
    (net (code "63") (name "unconnected-(U3-PB0-Pad14)") (class "Default")
      (node (ref "U3") (pin "14") (pinfunction "PB0_14") (pintype "passive"))
    )
    (net (code "64") (name "unconnected-(U3-PB2{slash}VSS2-Pad16)") (class "Default")
      (node (ref "U3") (pin "16") (pinfunction "PB2/VSS2_16") (pintype "passive"))
    )
    (net (code "65") (name "unconnected-(U3-PB3-Pad26)") (class "Default")
      (node (ref "U3") (pin "26") (pinfunction "PB3_26") (pintype "passive"))
    )
    (net (code "66") (name "unconnected-(U3-PB4-Pad27)") (class "Default")
      (node (ref "U3") (pin "27") (pinfunction "PB4_27") (pintype "passive"))
    )
    (net (code "67") (name "unconnected-(U3-PF0{slash}PC14-Pad2)") (class "Default")
      (node (ref "U3") (pin "2") (pinfunction "PF0/PC14_2") (pintype "passive"))
    )
    (net (code "68") (name "unconnected-(U3-PF1{slash}PC15-Pad3)") (class "Default")
      (node (ref "U3") (pin "3") (pinfunction "PF1/PC15_3") (pintype "passive"))
    )
  )
)
